# References.net
KiCad netlist of a schematic drawn in Altium Designer
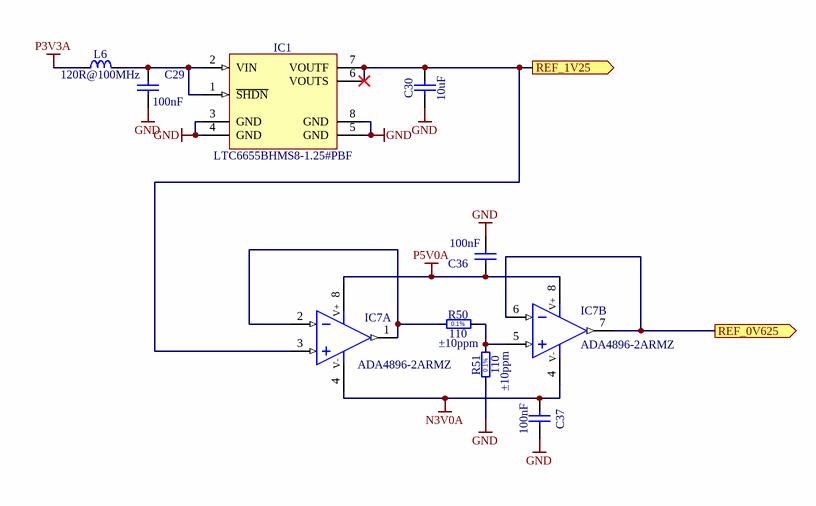
[diagram p0: References.SchDoc]

(export (version "E")
  (design (tool "Eeschema 10.0.6"))
  (components
    (comp (ref "C29")
      (value "100nF")
      (footprint "CAPC1005X55N")
      (description "Non-polarised capacitor")
      (fields
        (field (name "PART NUMBER") "CC0402_100NF_16V_10%_X7R")
        (field (name "VOLTAGE") "16V")
        (field (name "AUTHOR") "CERN DEM JLC")
      )
      (libsource (lib "Capacitors") (part "Capacitor - non polarized"))
    )
    (comp (ref "C30")
      (value "10uF")
      (footprint "CAPC1608X80N")
      (description "Non-polarised capacitor")
      (fields
        (field (name "PART NUMBER") "CC0603_10UF_16V_20%_X5R")
        (field (name "VOLTAGE") "16V")
        (field (name "AUTHOR") "CERN DEM MR")
      )
      (libsource (lib "Capacitors") (part "Capacitor - non polarized"))
    )
    (comp (ref "C36")
      (value "100nF")
      (footprint "CAPC0603X33N")
      (description "Non-polarised capacitor")
      (fields
        (field (name "PART NUMBER") "CC0201_100NF_6.3V_10%_X5R")
        (field (name "VOLTAGE") "6.3V")
        (field (name "AUTHOR") "CERN DEM JLC")
      )
      (libsource (lib "Capacitors") (part "Capacitor - non polarized"))
    )
    (comp (ref "C37")
      (value "100nF")
      (footprint "CAPC0603X33N")
      (description "Non-polarised capacitor")
      (fields
        (field (name "PART NUMBER") "CC0201_100NF_6.3V_10%_X5R")
        (field (name "VOLTAGE") "6.3V")
        (field (name "AUTHOR") "CERN DEM JLC")
      )
      (libsource (lib "Capacitors") (part "Capacitor - non polarized"))
    )
    (comp (ref "IC1")
      (value "LTC6655BHMS8-1.25#PBF")
      (footprint "SOP65P490X110-8N")
      (description "0.25ppm Noise, Low Drift Precision Buffered Voltage Reference")
      (fields (field (name "MANUFACTURER") "LINEAR TECHNOLOGY") (field (name "AUTHOR") "CERN DEM JLC"))
      (libsource (lib "ICs And Semiconductors") (part "LTC6655"))
    )
    (comp (ref "IC7")
      (value "ADA4896-2ARMZ")
      (footprint "SOP65P490X110-8N")
      (description "Dual Operational Amplifier")
      (fields (field (name "MANUFACTURER") "ANALOG DEVICES") (field (name "AUTHOR") "CERN DEM MR"))
      (libsource (lib "ICs And Semiconductors") (part "Operational Amplifier x2 Type1"))
    )
    (comp (ref "L6")
      (value "120R@100MHz")
      (footprint "INDC1608X65N")
      (description "Inductor")
      (fields
        (field (name "PART NUMBER") "IND0603_MURATA_BLM18SG121TN1D")
        (field (name "POWER") "3A")
        (field (name "AUTHOR") "CERN DEM JLC")
      )
      (libsource (lib "Inductors & Transformers") (part "Inductor"))
    )
    (comp (ref "R50")
      (value "110")
      (footprint "RESC1608X55N")
      (description "Resistor - 0.1%")
      (fields
        (field (name "PART NUMBER") "R0603_110R_0.1%_0.063W_10PPM")
        (field (name "POWER") "0.063W")
        (field (name "TC") "±10ppm")
        (field (name "AUTHOR") "CERN DEM JLC")
      )
      (libsource (lib "Resistors") (part "Resistor - 0.1%"))
    )
    (comp (ref "R51")
      (value "110")
      (footprint "RESC1608X55N")
      (description "Resistor - 0.1%")
      (fields
        (field (name "PART NUMBER") "R0603_110R_0.1%_0.063W_10PPM")
        (field (name "POWER") "0.063W")
        (field (name "TC") "±10ppm")
        (field (name "AUTHOR") "CERN DEM JLC")
      )
      (libsource (lib "Resistors") (part "Resistor - 0.1%"))
    )
  )
  (nets
    (net (code "1") (name "/REF_0V625") (class "Default")
      (node (ref "IC7") (pin "6") (pinfunction "IN-_6") (pintype "input"))
      (node (ref "IC7") (pin "7") (pinfunction "OUT_7") (pintype "output"))
    )
    (net (code "2") (name "/REF_1V25") (class "Default")
      (node (ref "C30") (pin "2") (pinfunction "2_2") (pintype "passive"))
      (node (ref "IC1") (pin "6") (pinfunction "VOUTS_6") (pintype "power_in"))
      (node (ref "IC1") (pin "7") (pinfunction "VOUTF_7") (pintype "power_in"))
      (node (ref "IC7") (pin "3") (pinfunction "IN+_3") (pintype "input"))
    )
    (net (code "3") (name "GND") (class "Default")
      (node (ref "C29") (pin "2") (pinfunction "2_2") (pintype "passive"))
      (node (ref "C30") (pin "1") (pinfunction "1_1") (pintype "passive"))
      (node (ref "C36") (pin "1") (pinfunction "1_1") (pintype "passive"))
      (node (ref "C37") (pin "1") (pinfunction "1_1") (pintype "passive"))
      (node (ref "IC1") (pin "3") (pinfunction "GND_3") (pintype "power_in"))
      (node (ref "IC1") (pin "4") (pinfunction "GND_4") (pintype "power_in"))
      (node (ref "IC1") (pin "5") (pinfunction "GND_5") (pintype "power_in"))
      (node (ref "IC1") (pin "8") (pinfunction "GND_8") (pintype "power_in"))
      (node (ref "R51") (pin "1") (pinfunction "1_1") (pintype "passive"))
    )
    (net (code "4") (name "N3V0A") (class "Default")
      (node (ref "C37") (pin "2") (pinfunction "2_2") (pintype "passive"))
      (node (ref "IC7") (pin "4") (pinfunction "V-_4") (pintype "power_in"))
    )
    (net (code "5") (name "Net-(IC1-VIN)") (class "Default")
      (node (ref "C29") (pin "1") (pinfunction "1_1") (pintype "passive"))
      (node (ref "IC1") (pin "1") (pinfunction "~{SHDN}_1") (pintype "input"))
      (node (ref "IC1") (pin "2") (pinfunction "VIN_2") (pintype "input"))
      (node (ref "L6") (pin "1") (pinfunction "1_1") (pintype "passive"))
    )
    (net (code "6") (name "Net-(IC7A-IN-)") (class "Default")
      (node (ref "IC7") (pin "1") (pinfunction "OUT_1") (pintype "output"))
      (node (ref "IC7") (pin "2") (pinfunction "IN-_2") (pintype "input"))
      (node (ref "R50") (pin "1") (pinfunction "1_1") (pintype "passive"))
    )
    (net (code "7") (name "Net-(IC7B-IN+)") (class "Default")
      (node (ref "IC7") (pin "5") (pinfunction "IN+_5") (pintype "input"))
      (node (ref "R50") (pin "2") (pinfunction "2_2") (pintype "passive"))
      (node (ref "R51") (pin "2") (pinfunction "2_2") (pintype "passive"))
    )
    (net (code "8") (name "P3V3A") (class "Default")
      (node (ref "L6") (pin "2") (pinfunction "2_2") (pintype "passive"))
    )
    (net (code "9") (name "P5V0A") (class "Default")
      (node (ref "C36") (pin "2") (pinfunction "2_2") (pintype "passive"))
      (node (ref "IC7") (pin "8") (pinfunction "V+_8") (pintype "power_in"))
    )
  )
)
